# ignition7.net
KiCad netlist of a schematic drawn in EAGLE
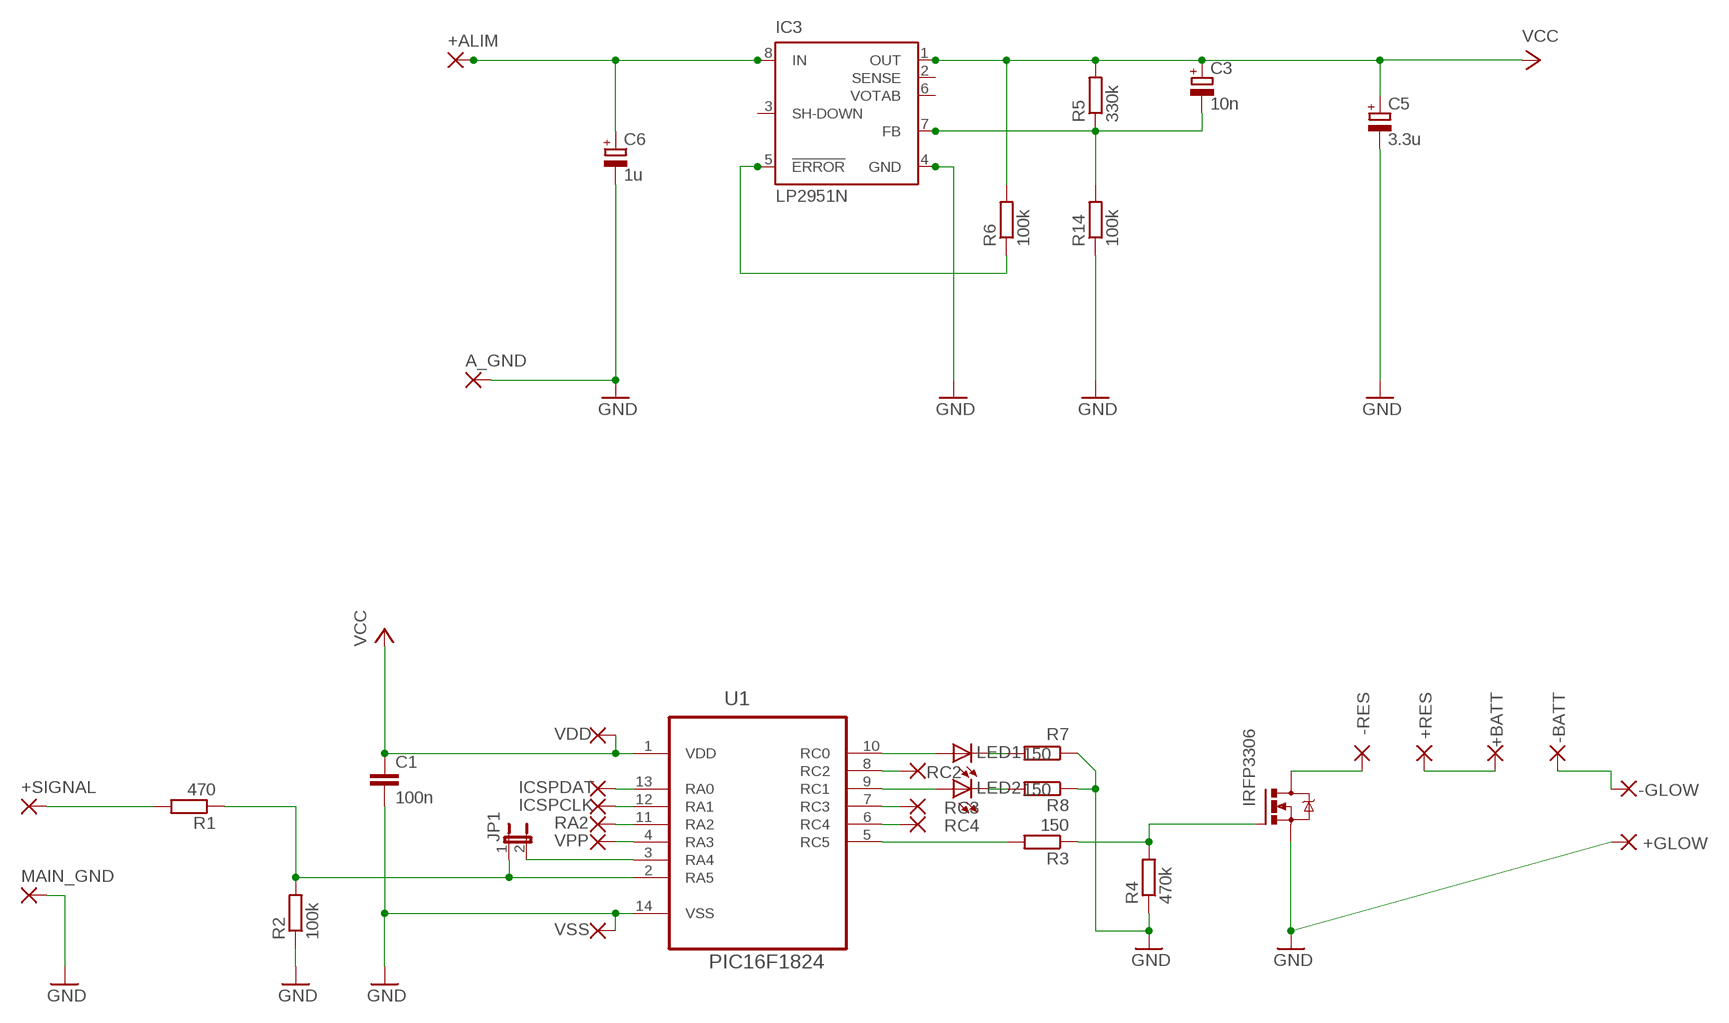
[diagram p0: schematic, sheet 1]

(export (version "E")
  (design (tool "Eeschema 10.0.6"))
  (components
    (comp (ref "+ALIM")
      (value "2,15/1,0")
      (footprint "eagle-import:2,15_1,0")
      (libsource (lib "eagle-import") (part "2,15/1,0"))
    )
    (comp (ref "+BATT")
      (value "WIREPAD3,17/1,3")
      (footprint "eagle-import:3,17_1,3")
      (libsource (lib "eagle-import") (part "WIREPAD3,17/1,3"))
    )
    (comp (ref "+GLOW")
      (value "WIREPAD3,17/1,3")
      (footprint "eagle-import:3,17_1,3")
      (libsource (lib "eagle-import") (part "WIREPAD3,17/1,3"))
    )
    (comp (ref "+RES")
      (value "WIREPAD3,17/1,3")
      (footprint "eagle-import:3,17_1,3")
      (libsource (lib "eagle-import") (part "WIREPAD3,17/1,3"))
    )
    (comp (ref "+SIGNAL")
      (value "2,15/1,0")
      (footprint "eagle-import:2,15_1,0")
      (libsource (lib "eagle-import") (part "2,15/1,0"))
    )
    (comp (ref "-BATT")
      (value "WIREPAD3,17/1,3")
      (footprint "eagle-import:3,17_1,3")
      (libsource (lib "eagle-import") (part "WIREPAD3,17/1,3"))
    )
    (comp (ref "-GLOW")
      (value "WIREPAD3,17/1,3")
      (footprint "eagle-import:3,17_1,3")
      (libsource (lib "eagle-import") (part "WIREPAD3,17/1,3"))
    )
    (comp (ref "-RES")
      (value "WIREPAD3,17/1,3")
      (footprint "eagle-import:3,17_1,3")
      (libsource (lib "eagle-import") (part "WIREPAD3,17/1,3"))
    )
    (comp (ref "A_GND")
      (value "WIREPAD1,6/0,9")
      (footprint "eagle-import:1,6_0,9")
      (libsource (lib "eagle-import") (part "WIREPAD1,6/0,9"))
    )
    (comp (ref "C1")
      (value "100n")
      (footprint "eagle-import:C050-035X075")
      (libsource (lib "eagle-import") (part "C-EU050-035X075"))
    )
    (comp (ref "C3")
      (value "10n")
      (footprint "eagle-import:E5-6")
      (libsource (lib "eagle-import") (part "CPOL-EUE5-6"))
    )
    (comp (ref "C5")
      (value "3.3u")
      (footprint "eagle-import:E2,5-5")
      (libsource (lib "eagle-import") (part "CPOL-EUE2.5-5"))
    )
    (comp (ref "C6")
      (value "1u")
      (footprint "eagle-import:E2,5-5")
      (libsource (lib "eagle-import") (part "CPOL-EUE2.5-5"))
    )
    (comp (ref "IC3")
      (value "LP2951N")
      (footprint "eagle-import:DIL08")
      (libsource (lib "eagle-import") (part "LP2951N"))
    )
    (comp (ref "ICSPCLK")
      (value "2,15/1,0")
      (footprint "eagle-import:2,15_1,0")
      (libsource (lib "eagle-import") (part "2,15/1,0"))
    )
    (comp (ref "ICSPDAT")
      (value "2,15/1,0")
      (footprint "eagle-import:2,15_1,0")
      (libsource (lib "eagle-import") (part "2,15/1,0"))
    )
    (comp (ref "JP1")
      (value "JP1E")
      (footprint "eagle-import:JP1")
      (libsource (lib "eagle-import") (part "JP1E"))
    )
    (comp (ref "LED1")
      (value "LED3MM")
      (footprint "eagle-import:LED3MM")
      (libsource (lib "eagle-import") (part "LED3MM"))
    )
    (comp (ref "LED2")
      (value "LED3MM")
      (footprint "eagle-import:LED3MM")
      (libsource (lib "eagle-import") (part "LED3MM"))
    )
    (comp (ref "MAIN_GND")
      (value "WIREPAD1,6/0,9")
      (footprint "eagle-import:1,6_0,9")
      (libsource (lib "eagle-import") (part "WIREPAD1,6/0,9"))
    )
    (comp (ref "Q2")
      (value "IRFP3306")
      (footprint "eagle-import:TO247BV")
      (libsource (lib "eagle-import") (part "IRFPC40"))
    )
    (comp (ref "R1")
      (value "470")
      (footprint "eagle-import:0207_7")
      (libsource (lib "eagle-import") (part "R-EU_0207/7"))
    )
    (comp (ref "R2")
      (value "100k")
      (footprint "eagle-import:0207_7")
      (libsource (lib "eagle-import") (part "R-EU_0207/7"))
    )
    (comp (ref "R3")
      (value "150")
      (footprint "eagle-import:0207_7")
      (libsource (lib "eagle-import") (part "R-EU_0207/7"))
    )
    (comp (ref "R4")
      (value "470k")
      (footprint "eagle-import:0207_7")
      (libsource (lib "eagle-import") (part "R-EU_0207/7"))
    )
    (comp (ref "R5")
      (value "330k")
      (footprint "eagle-import:0207_7")
      (libsource (lib "eagle-import") (part "R-EU_0207/7"))
    )
    (comp (ref "R6")
      (value "100k")
      (footprint "eagle-import:0207_7")
      (libsource (lib "eagle-import") (part "R-EU_0207/7"))
    )
    (comp (ref "R7")
      (value "150")
      (footprint "eagle-import:0207_7")
      (libsource (lib "eagle-import") (part "R-EU_0207/7"))
    )
    (comp (ref "R8")
      (value "150")
      (footprint "eagle-import:0207_7")
      (libsource (lib "eagle-import") (part "R-EU_0207/7"))
    )
    (comp (ref "R14")
      (value "100k")
      (footprint "eagle-import:0207_7")
      (libsource (lib "eagle-import") (part "R-EU_0207/7"))
    )
    (comp (ref "RA2")
      (value "2,15/1,0")
      (footprint "eagle-import:2,15_1,0")
      (libsource (lib "eagle-import") (part "2,15/1,0"))
    )
    (comp (ref "RC2")
      (value "2,15/1,0")
      (footprint "eagle-import:2,15_1,0")
      (libsource (lib "eagle-import") (part "2,15/1,0"))
    )
    (comp (ref "RC3")
      (value "2,15/1,0")
      (footprint "eagle-import:2,15_1,0")
      (libsource (lib "eagle-import") (part "2,15/1,0"))
    )
    (comp (ref "RC4")
      (value "2,15/1,0")
      (footprint "eagle-import:2,15_1,0")
      (libsource (lib "eagle-import") (part "2,15/1,0"))
    )
    (comp (ref "U1")
      (value "PIC16F1824")
      (footprint "eagle-import:DIP254P762X533-14")
      (fields (field (name "MPN") "PIC16F1824-I/P"))
      (libsource (lib "eagle-import") (part "PIC16F1824-I/P"))
    )
    (comp (ref "VDD")
      (value "WIREPAD2,15/1,0")
      (footprint "eagle-import:2,15_1,0")
      (libsource (lib "eagle-import") (part "WIREPAD2,15/1,0"))
    )
    (comp (ref "VPP")
      (value "2,15/1,0")
      (footprint "eagle-import:2,15_1,0")
      (libsource (lib "eagle-import") (part "2,15/1,0"))
    )
    (comp (ref "VSS")
      (value "WIREPAD1,6/0,9")
      (footprint "eagle-import:1,6_0,9")
      (libsource (lib "eagle-import") (part "WIREPAD1,6/0,9"))
    )
  )
  (nets
    (net (code "1") (name "GND") (class "Default")
      (node (ref "+GLOW") (pin "1") (pinfunction "P_1") (pintype "passive"))
      (node (ref "A_GND") (pin "1") (pinfunction "P_1") (pintype "passive"))
      (node (ref "C1") (pin "2") (pinfunction "2_2") (pintype "passive"))
      (node (ref "C5") (pin "-") (pinfunction "-_-") (pintype "passive"))
      (node (ref "C6") (pin "-") (pinfunction "-_-") (pintype "passive"))
      (node (ref "IC3") (pin "4") (pinfunction "GND_4") (pintype "power_in"))
      (node (ref "MAIN_GND") (pin "1") (pinfunction "P_1") (pintype "passive"))
      (node (ref "Q2") (pin "S") (pinfunction "S_S") (pintype "passive"))
      (node (ref "R14") (pin "1") (pinfunction "1_1") (pintype "passive"))
      (node (ref "R2") (pin "1") (pinfunction "1_1") (pintype "passive"))
      (node (ref "R4") (pin "1") (pinfunction "1_1") (pintype "passive"))
      (node (ref "R7") (pin "1") (pinfunction "1_1") (pintype "passive"))
      (node (ref "R8") (pin "1") (pinfunction "1_1") (pintype "passive"))
      (node (ref "U1") (pin "14") (pinfunction "VSS_14") (pintype "power_in"))
      (node (ref "VSS") (pin "1") (pinfunction "P_1") (pintype "passive"))
    )
    (net (code "2") (name "Net-(+ALIM-P)") (class "Default")
      (node (ref "+ALIM") (pin "1") (pinfunction "P_1") (pintype "passive"))
      (node (ref "C6") (pin "+") (pinfunction "+_+") (pintype "passive"))
      (node (ref "IC3") (pin "8") (pinfunction "IN_8") (pintype "input"))
    )
    (net (code "3") (name "Net-(+BATT-P)") (class "Default")
      (node (ref "+BATT") (pin "1") (pinfunction "P_1") (pintype "passive"))
      (node (ref "+RES") (pin "1") (pinfunction "P_1") (pintype "passive"))
    )
    (net (code "4") (name "Net-(+SIGNAL-P)") (class "Default")
      (node (ref "+SIGNAL") (pin "1") (pinfunction "P_1") (pintype "passive"))
      (node (ref "R1") (pin "2") (pinfunction "2_2") (pintype "passive"))
    )
    (net (code "5") (name "Net-(-BATT-P)") (class "Default")
      (node (ref "-BATT") (pin "1") (pinfunction "P_1") (pintype "passive"))
      (node (ref "-GLOW") (pin "1") (pinfunction "P_1") (pintype "passive"))
    )
    (net (code "6") (name "Net-(-RES-P)") (class "Default")
      (node (ref "-RES") (pin "1") (pinfunction "P_1") (pintype "passive"))
      (node (ref "Q2") (pin "D") (pinfunction "D_D") (pintype "passive"))
    )
    (net (code "7") (name "Net-(IC3-FB)") (class "Default")
      (node (ref "C3") (pin "-") (pinfunction "-_-") (pintype "passive"))
      (node (ref "IC3") (pin "7") (pinfunction "FB_7") (pintype "input"))
      (node (ref "R14") (pin "2") (pinfunction "2_2") (pintype "passive"))
      (node (ref "R5") (pin "1") (pinfunction "1_1") (pintype "passive"))
    )
    (net (code "8") (name "Net-(IC3-~{ERROR})") (class "Default")
      (node (ref "IC3") (pin "5") (pinfunction "~{ERROR}_5") (pintype "output"))
      (node (ref "R6") (pin "1") (pinfunction "1_1") (pintype "passive"))
    )
    (net (code "9") (name "Net-(ICSPCLK-P)") (class "Default")
      (node (ref "ICSPCLK") (pin "1") (pinfunction "P_1") (pintype "passive"))
      (node (ref "U1") (pin "12") (pinfunction "RA1_12") (pintype "bidirectional"))
    )
    (net (code "10") (name "Net-(ICSPDAT-P)") (class "Default")
      (node (ref "ICSPDAT") (pin "1") (pinfunction "P_1") (pintype "passive"))
      (node (ref "U1") (pin "13") (pinfunction "RA0_13") (pintype "bidirectional"))
    )
    (net (code "11") (name "Net-(LED1-C)") (class "Default")
      (node (ref "LED1") (pin "K") (pinfunction "C_K") (pintype "passive"))
      (node (ref "R7") (pin "2") (pinfunction "2_2") (pintype "passive"))
    )
    (net (code "12") (name "Net-(LED2-C)") (class "Default")
      (node (ref "LED2") (pin "K") (pinfunction "C_K") (pintype "passive"))
      (node (ref "R8") (pin "2") (pinfunction "2_2") (pintype "passive"))
    )
    (net (code "13") (name "Net-(Q2-PadG)") (class "Default")
      (node (ref "Q2") (pin "G") (pinfunction "G_G") (pintype "passive"))
      (node (ref "R3") (pin "1") (pinfunction "1_1") (pintype "passive"))
      (node (ref "R4") (pin "2") (pinfunction "2_2") (pintype "passive"))
    )
    (net (code "14") (name "Net-(RA2-P)") (class "Default")
      (node (ref "RA2") (pin "1") (pinfunction "P_1") (pintype "passive"))
      (node (ref "U1") (pin "11") (pinfunction "RA2_11") (pintype "bidirectional"))
    )
    (net (code "15") (name "Net-(RC2-P)") (class "Default")
      (node (ref "RC2") (pin "1") (pinfunction "P_1") (pintype "passive"))
      (node (ref "U1") (pin "8") (pinfunction "RC2_8") (pintype "bidirectional"))
    )
    (net (code "16") (name "Net-(RC3-P)") (class "Default")
      (node (ref "RC3") (pin "1") (pinfunction "P_1") (pintype "passive"))
      (node (ref "U1") (pin "7") (pinfunction "RC3_7") (pintype "bidirectional"))
    )
    (net (code "17") (name "Net-(RC4-P)") (class "Default")
      (node (ref "RC4") (pin "1") (pinfunction "P_1") (pintype "passive"))
      (node (ref "U1") (pin "6") (pinfunction "RC4_6") (pintype "bidirectional"))
    )
    (net (code "18") (name "Net-(U1-RA3)") (class "Default")
      (node (ref "U1") (pin "4") (pinfunction "RA3_4") (pintype "input"))
      (node (ref "VPP") (pin "1") (pinfunction "P_1") (pintype "passive"))
    )
    (net (code "19") (name "Net-(U1-RA4)") (class "Default")
      (node (ref "JP1") (pin "2") (pinfunction "2_2") (pintype "passive"))
      (node (ref "U1") (pin "3") (pinfunction "RA4_3") (pintype "bidirectional"))
    )
    (net (code "20") (name "Net-(U1-RA5)") (class "Default")
      (node (ref "JP1") (pin "1") (pinfunction "1_1") (pintype "passive"))
      (node (ref "R1") (pin "1") (pinfunction "1_1") (pintype "passive"))
      (node (ref "R2") (pin "2") (pinfunction "2_2") (pintype "passive"))
      (node (ref "U1") (pin "2") (pinfunction "RA5_2") (pintype "bidirectional"))
    )
    (net (code "21") (name "Net-(U1-RC0)") (class "Default")
      (node (ref "LED1") (pin "A") (pinfunction "A_A") (pintype "passive"))
      (node (ref "U1") (pin "10") (pinfunction "RC0_10") (pintype "bidirectional"))
    )
    (net (code "22") (name "Net-(U1-RC1)") (class "Default")
      (node (ref "LED2") (pin "A") (pinfunction "A_A") (pintype "passive"))
      (node (ref "U1") (pin "9") (pinfunction "RC1_9") (pintype "bidirectional"))
    )
    (net (code "23") (name "Net-(U1-RC5)") (class "Default")
      (node (ref "R3") (pin "2") (pinfunction "2_2") (pintype "passive"))
      (node (ref "U1") (pin "5") (pinfunction "RC5_5") (pintype "bidirectional"))
    )
    (net (code "24") (name "VCC") (class "Default")
      (node (ref "C1") (pin "1") (pinfunction "1_1") (pintype "passive"))
      (node (ref "C3") (pin "+") (pinfunction "+_+") (pintype "passive"))
      (node (ref "C5") (pin "+") (pinfunction "+_+") (pintype "passive"))
      (node (ref "IC3") (pin "1") (pinfunction "OUT_1") (pintype "input"))
      (node (ref "R5") (pin "2") (pinfunction "2_2") (pintype "passive"))
      (node (ref "R6") (pin "2") (pinfunction "2_2") (pintype "passive"))
      (node (ref "U1") (pin "1") (pinfunction "VDD_1") (pintype "power_in"))
      (node (ref "VDD") (pin "1") (pinfunction "P_1") (pintype "passive"))
    )
    (net (code "25") (name "unconnected-(IC3-SENSE-Pad2)") (class "Default")
      (node (ref "IC3") (pin "2") (pinfunction "SENSE_2") (pintype "input"))
    )
    (net (code "26") (name "unconnected-(IC3-SH-DOWN-Pad3)") (class "Default")
      (node (ref "IC3") (pin "3") (pinfunction "SH-DOWN_3") (pintype "input"))
    )
    (net (code "27") (name "unconnected-(IC3-VOTAB-Pad6)") (class "Default")
      (node (ref "IC3") (pin "6") (pinfunction "VOTAB_6") (pintype "passive"))
    )
  )
)
